# RPi-UKHASnet-node.net
KiCad netlist of a schematic drawn in EAGLE
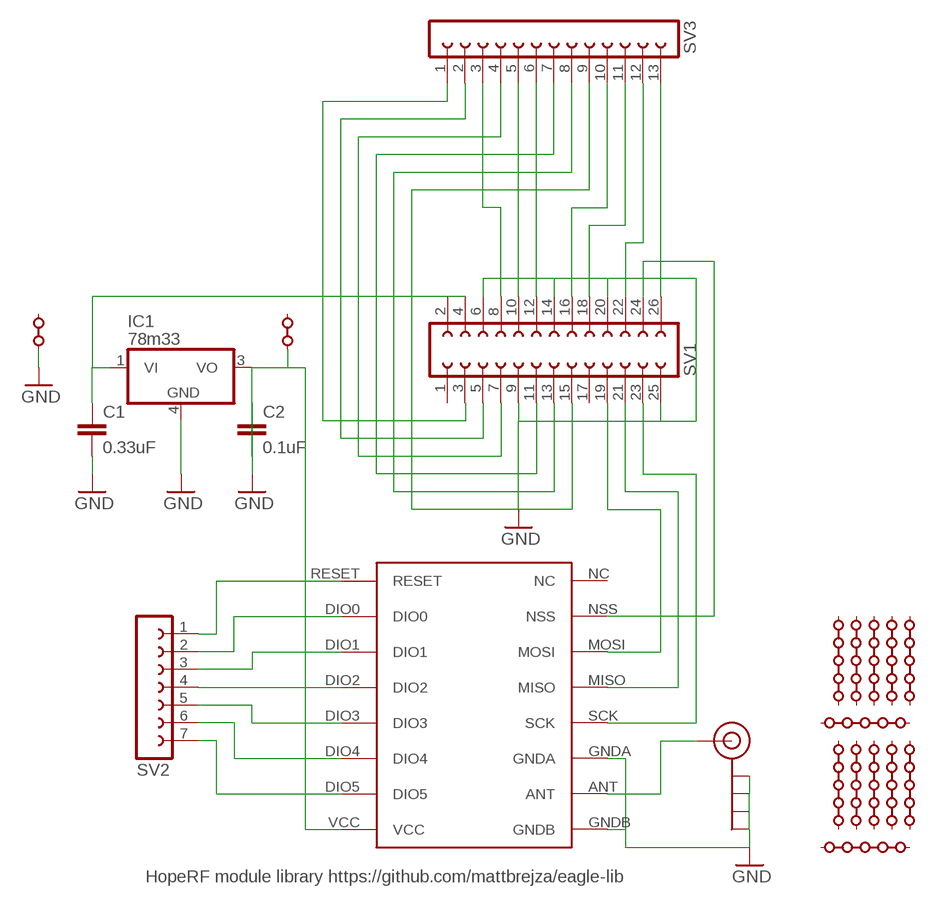
[diagram p0: schematic, sheet 1]

(export (version "E")
  (design (tool "Eeschema 10.0.6"))
  (components
    (comp (ref "C1")
      (value "0.33uF")
      (footprint "eagle-import:C1206")
      (libsource (lib "eagle-import") (part "C-EUC1206"))
    )
    (comp (ref "C2")
      (value "0.1uF")
      (footprint "eagle-import:C1206")
      (libsource (lib "eagle-import") (part "C-EUC1206"))
    )
    (comp (ref "IC1")
      (value "78m33")
      (footprint "eagle-import:SOT223")
      (libsource (lib "eagle-import") (part "LM340?-MP05"))
    )
    (comp (ref "J$1")
      (value "SMA_EDGE")
      (footprint "eagle-import:SMA-EDGE")
      (libsource (lib "eagle-import") (part "SMA_EDGE"))
    )
    (comp (ref "P1")
      (value "PADSTRIP5-VA")
      (footprint "eagle-import:PADSTRIP-5V")
      (libsource (lib "eagle-import") (part "PADSTRIP5-VA"))
    )
    (comp (ref "P2")
      (value "PADSTRIP5-VA")
      (footprint "eagle-import:PADSTRIP-5V")
      (libsource (lib "eagle-import") (part "PADSTRIP5-VA"))
    )
    (comp (ref "P3")
      (value "PADSTRIP5-VA")
      (footprint "eagle-import:PADSTRIP-5V")
      (libsource (lib "eagle-import") (part "PADSTRIP5-VA"))
    )
    (comp (ref "P4")
      (value "PADSTRIP5-VA")
      (footprint "eagle-import:PADSTRIP-5V")
      (libsource (lib "eagle-import") (part "PADSTRIP5-VA"))
    )
    (comp (ref "P5")
      (value "PADSTRIP5-VA")
      (footprint "eagle-import:PADSTRIP-5V")
      (libsource (lib "eagle-import") (part "PADSTRIP5-VA"))
    )
    (comp (ref "P9")
      (value "PADSTRIP5-VA")
      (footprint "eagle-import:PADSTRIP-5V")
      (libsource (lib "eagle-import") (part "PADSTRIP5-VA"))
    )
    (comp (ref "P10")
      (value "PADSTRIP5-VA")
      (footprint "eagle-import:PADSTRIP-5V")
      (libsource (lib "eagle-import") (part "PADSTRIP5-VA"))
    )
    (comp (ref "P11")
      (value "PADSTRIP5-VA")
      (footprint "eagle-import:PADSTRIP-5V")
      (libsource (lib "eagle-import") (part "PADSTRIP5-VA"))
    )
    (comp (ref "P12")
      (value "PADSTRIP5-VA")
      (footprint "eagle-import:PADSTRIP-5V")
      (libsource (lib "eagle-import") (part "PADSTRIP5-VA"))
    )
    (comp (ref "P13")
      (value "PADSTRIP5-VA")
      (footprint "eagle-import:PADSTRIP-5V")
      (libsource (lib "eagle-import") (part "PADSTRIP5-VA"))
    )
    (comp (ref "P17")
      (value "PADSTRIP5-VA")
      (footprint "eagle-import:PADSTRIP-5V")
      (libsource (lib "eagle-import") (part "PADSTRIP5-VA"))
    )
    (comp (ref "P18")
      (value "PADSTRIP5-VA")
      (footprint "eagle-import:PADSTRIP-5V")
      (libsource (lib "eagle-import") (part "PADSTRIP5-VA"))
    )
    (comp (ref "PR8")
      (value "PADSTRIP2-H")
      (footprint "eagle-import:PADSTRIP-2H")
      (libsource (lib "eagle-import") (part "PADSTRIP2-H"))
    )
    (comp (ref "PR20")
      (value "PADSTRIP2-H")
      (footprint "eagle-import:PADSTRIP-2H")
      (libsource (lib "eagle-import") (part "PADSTRIP2-H"))
    )
    (comp (ref "SV1")
      (value "FE13-2")
      (footprint "eagle-import:FE13-2")
      (libsource (lib "eagle-import") (part "FE13-2"))
    )
    (comp (ref "SV2")
      (value "FE07-1")
      (footprint "eagle-import:FE07")
      (libsource (lib "eagle-import") (part "FE07-1"))
    )
    (comp (ref "SV3")
      (value "FE13-1")
      (footprint "eagle-import:FE13")
      (libsource (lib "eagle-import") (part "FE13-1"))
    )
    (comp (ref "U1")
      (value "RFM69HW")
      (footprint "eagle-import:RFM")
      (libsource (lib "eagle-import") (part "RFM69HW"))
    )
  )
  (nets
    (net (code "1") (name "GND") (class "Default")
      (node (ref "C1") (pin "2") (pinfunction "2_2") (pintype "passive"))
      (node (ref "C2") (pin "1") (pinfunction "1_1") (pintype "passive"))
      (node (ref "IC1") (pin "4") (pinfunction "GND_4") (pintype "passive"))
      (node (ref "J$1") (pin "GND@0") (pinfunction "GND_GND@0") (pintype "bidirectional"))
      (node (ref "J$1") (pin "GND@1") (pinfunction "GND_GND@1") (pintype "bidirectional"))
      (node (ref "J$1") (pin "GND@2") (pinfunction "GND_GND@2") (pintype "bidirectional"))
      (node (ref "J$1") (pin "GND@3") (pinfunction "GND_GND@3") (pintype "bidirectional"))
      (node (ref "PR20") (pin "1") (pinfunction "LFT_1") (pintype "bidirectional"))
      (node (ref "SV1") (pin "14") (pinfunction "14_14") (pintype "passive"))
      (node (ref "SV1") (pin "20") (pinfunction "20_20") (pintype "passive"))
      (node (ref "SV1") (pin "25") (pinfunction "25_25") (pintype "passive"))
      (node (ref "SV1") (pin "6") (pinfunction "6_6") (pintype "passive"))
      (node (ref "SV1") (pin "9") (pinfunction "9_9") (pintype "passive"))
      (node (ref "U1") (pin "GNDA") (pinfunction "GNDA_GNDA") (pintype "bidirectional"))
      (node (ref "U1") (pin "GNDB") (pinfunction "GNDB_GNDB") (pintype "bidirectional"))
    )
    (net (code "2") (name "Net-(IC1-VI)") (class "Default")
      (node (ref "C1") (pin "1") (pinfunction "1_1") (pintype "passive"))
      (node (ref "IC1") (pin "1") (pinfunction "VI_1") (pintype "input"))
      (node (ref "SV1") (pin "2") (pinfunction "2_2") (pintype "passive"))
      (node (ref "SV1") (pin "4") (pinfunction "4_4") (pintype "passive"))
    )
    (net (code "3") (name "Net-(IC1-VO)") (class "Default")
      (node (ref "C2") (pin "2") (pinfunction "2_2") (pintype "passive"))
      (node (ref "IC1") (pin "3") (pinfunction "VO_3") (pintype "passive"))
      (node (ref "PR8") (pin "1") (pinfunction "LFT_1") (pintype "bidirectional"))
      (node (ref "U1") (pin "VCC") (pinfunction "VCC_VCC") (pintype "bidirectional"))
    )
    (net (code "4") (name "Net-(J$1-SIGNAL)") (class "Default")
      (node (ref "J$1") (pin "SIG") (pinfunction "SIGNAL_SIG") (pintype "bidirectional"))
      (node (ref "U1") (pin "ANT") (pinfunction "ANT_ANT") (pintype "bidirectional"))
    )
    (net (code "5") (name "Net-(SV1-Pad3)") (class "Default")
      (node (ref "SV1") (pin "3") (pinfunction "3_3") (pintype "passive"))
      (node (ref "SV3") (pin "1") (pinfunction "1_1") (pintype "passive"))
    )
    (net (code "6") (name "Net-(SV1-Pad5)") (class "Default")
      (node (ref "SV1") (pin "5") (pinfunction "5_5") (pintype "passive"))
      (node (ref "SV3") (pin "2") (pinfunction "2_2") (pintype "passive"))
    )
    (net (code "7") (name "Net-(SV1-Pad7)") (class "Default")
      (node (ref "SV1") (pin "7") (pinfunction "7_7") (pintype "passive"))
      (node (ref "SV3") (pin "4") (pinfunction "4_4") (pintype "passive"))
    )
    (net (code "8") (name "Net-(SV1-Pad8)") (class "Default")
      (node (ref "SV1") (pin "8") (pinfunction "8_8") (pintype "passive"))
      (node (ref "SV3") (pin "3") (pinfunction "3_3") (pintype "passive"))
    )
    (net (code "9") (name "Net-(SV1-Pad10)") (class "Default")
      (node (ref "SV1") (pin "10") (pinfunction "10_10") (pintype "passive"))
      (node (ref "SV3") (pin "5") (pinfunction "5_5") (pintype "passive"))
    )
    (net (code "10") (name "Net-(SV1-Pad11)") (class "Default")
      (node (ref "SV1") (pin "11") (pinfunction "11_11") (pintype "passive"))
      (node (ref "SV3") (pin "7") (pinfunction "7_7") (pintype "passive"))
    )
    (net (code "11") (name "Net-(SV1-Pad12)") (class "Default")
      (node (ref "SV1") (pin "12") (pinfunction "12_12") (pintype "passive"))
      (node (ref "SV3") (pin "6") (pinfunction "6_6") (pintype "passive"))
    )
    (net (code "12") (name "Net-(SV1-Pad13)") (class "Default")
      (node (ref "SV1") (pin "13") (pinfunction "13_13") (pintype "passive"))
      (node (ref "SV3") (pin "8") (pinfunction "8_8") (pintype "passive"))
    )
    (net (code "13") (name "Net-(SV1-Pad15)") (class "Default")
      (node (ref "SV1") (pin "15") (pinfunction "15_15") (pintype "passive"))
      (node (ref "SV3") (pin "9") (pinfunction "9_9") (pintype "passive"))
    )
    (net (code "14") (name "Net-(SV1-Pad16)") (class "Default")
      (node (ref "SV1") (pin "16") (pinfunction "16_16") (pintype "passive"))
      (node (ref "SV3") (pin "10") (pinfunction "10_10") (pintype "passive"))
    )
    (net (code "15") (name "Net-(SV1-Pad18)") (class "Default")
      (node (ref "SV1") (pin "18") (pinfunction "18_18") (pintype "passive"))
      (node (ref "SV3") (pin "11") (pinfunction "11_11") (pintype "passive"))
    )
    (net (code "16") (name "Net-(SV1-Pad19)") (class "Default")
      (node (ref "SV1") (pin "19") (pinfunction "19_19") (pintype "passive"))
      (node (ref "U1") (pin "MOSI") (pinfunction "MOSI_MOSI") (pintype "bidirectional"))
    )
    (net (code "17") (name "Net-(SV1-Pad21)") (class "Default")
      (node (ref "SV1") (pin "21") (pinfunction "21_21") (pintype "passive"))
      (node (ref "U1") (pin "MISO") (pinfunction "MISO_MISO") (pintype "bidirectional"))
    )
    (net (code "18") (name "Net-(SV1-Pad22)") (class "Default")
      (node (ref "SV1") (pin "22") (pinfunction "22_22") (pintype "passive"))
      (node (ref "SV3") (pin "12") (pinfunction "12_12") (pintype "passive"))
    )
    (net (code "19") (name "Net-(SV1-Pad23)") (class "Default")
      (node (ref "SV1") (pin "23") (pinfunction "23_23") (pintype "passive"))
      (node (ref "U1") (pin "SCK") (pinfunction "SCK_SCK") (pintype "bidirectional"))
    )
    (net (code "20") (name "Net-(SV1-Pad24)") (class "Default")
      (node (ref "SV1") (pin "24") (pinfunction "24_24") (pintype "passive"))
      (node (ref "U1") (pin "NSS") (pinfunction "NSS_NSS") (pintype "bidirectional"))
    )
    (net (code "21") (name "Net-(SV1-Pad26)") (class "Default")
      (node (ref "SV1") (pin "26") (pinfunction "26_26") (pintype "passive"))
      (node (ref "SV3") (pin "13") (pinfunction "13_13") (pintype "passive"))
    )
    (net (code "22") (name "Net-(SV2-Pad1)") (class "Default")
      (node (ref "SV2") (pin "1") (pinfunction "1_1") (pintype "passive"))
      (node (ref "U1") (pin "RESET") (pinfunction "RESET_RESET") (pintype "bidirectional"))
    )
    (net (code "23") (name "Net-(SV2-Pad2)") (class "Default")
      (node (ref "SV2") (pin "2") (pinfunction "2_2") (pintype "passive"))
      (node (ref "U1") (pin "DIO0") (pinfunction "DIO0_DIO0") (pintype "bidirectional"))
    )
    (net (code "24") (name "Net-(SV2-Pad3)") (class "Default")
      (node (ref "SV2") (pin "3") (pinfunction "3_3") (pintype "passive"))
      (node (ref "U1") (pin "DIO1") (pinfunction "DIO1_DIO1") (pintype "bidirectional"))
    )
    (net (code "25") (name "Net-(SV2-Pad4)") (class "Default")
      (node (ref "SV2") (pin "4") (pinfunction "4_4") (pintype "passive"))
      (node (ref "U1") (pin "DIO2") (pinfunction "DIO2_DIO2") (pintype "bidirectional"))
    )
    (net (code "26") (name "Net-(SV2-Pad5)") (class "Default")
      (node (ref "SV2") (pin "5") (pinfunction "5_5") (pintype "passive"))
      (node (ref "U1") (pin "DIO3") (pinfunction "DIO3_DIO3") (pintype "bidirectional"))
    )
    (net (code "27") (name "Net-(SV2-Pad6)") (class "Default")
      (node (ref "SV2") (pin "6") (pinfunction "6_6") (pintype "passive"))
      (node (ref "U1") (pin "DIO4") (pinfunction "DIO4_DIO4") (pintype "bidirectional"))
    )
    (net (code "28") (name "Net-(SV2-Pad7)") (class "Default")
      (node (ref "SV2") (pin "7") (pinfunction "7_7") (pintype "passive"))
      (node (ref "U1") (pin "DIO5") (pinfunction "DIO5_DIO5") (pintype "bidirectional"))
    )
    (net (code "29") (name "unconnected-(P1-Pad1)") (class "Default")
      (node (ref "P1") (pin "1") (pinfunction "1_1") (pintype "bidirectional"))
    )
    (net (code "30") (name "unconnected-(P1-Pad5)") (class "Default")
      (node (ref "P1") (pin "5") (pinfunction "5_5") (pintype "bidirectional"))
    )
    (net (code "31") (name "unconnected-(P2-Pad1)") (class "Default")
      (node (ref "P2") (pin "1") (pinfunction "1_1") (pintype "bidirectional"))
    )
    (net (code "32") (name "unconnected-(P2-Pad5)") (class "Default")
      (node (ref "P2") (pin "5") (pinfunction "5_5") (pintype "bidirectional"))
    )
    (net (code "33") (name "unconnected-(P3-Pad1)") (class "Default")
      (node (ref "P3") (pin "1") (pinfunction "1_1") (pintype "bidirectional"))
    )
    (net (code "34") (name "unconnected-(P3-Pad5)") (class "Default")
      (node (ref "P3") (pin "5") (pinfunction "5_5") (pintype "bidirectional"))
    )
    (net (code "35") (name "unconnected-(P4-Pad1)") (class "Default")
      (node (ref "P4") (pin "1") (pinfunction "1_1") (pintype "bidirectional"))
    )
    (net (code "36") (name "unconnected-(P4-Pad5)") (class "Default")
      (node (ref "P4") (pin "5") (pinfunction "5_5") (pintype "bidirectional"))
    )
    (net (code "37") (name "unconnected-(P5-Pad1)") (class "Default")
      (node (ref "P5") (pin "1") (pinfunction "1_1") (pintype "bidirectional"))
    )
    (net (code "38") (name "unconnected-(P5-Pad5)") (class "Default")
      (node (ref "P5") (pin "5") (pinfunction "5_5") (pintype "bidirectional"))
    )
    (net (code "39") (name "unconnected-(P9-Pad1)") (class "Default")
      (node (ref "P9") (pin "1") (pinfunction "1_1") (pintype "bidirectional"))
    )
    (net (code "40") (name "unconnected-(P9-Pad5)") (class "Default")
      (node (ref "P9") (pin "5") (pinfunction "5_5") (pintype "bidirectional"))
    )
    (net (code "41") (name "unconnected-(P10-Pad1)") (class "Default")
      (node (ref "P10") (pin "1") (pinfunction "1_1") (pintype "bidirectional"))
    )
    (net (code "42") (name "unconnected-(P10-Pad5)") (class "Default")
      (node (ref "P10") (pin "5") (pinfunction "5_5") (pintype "bidirectional"))
    )
    (net (code "43") (name "unconnected-(P11-Pad1)") (class "Default")
      (node (ref "P11") (pin "1") (pinfunction "1_1") (pintype "bidirectional"))
    )
    (net (code "44") (name "unconnected-(P11-Pad5)") (class "Default")
      (node (ref "P11") (pin "5") (pinfunction "5_5") (pintype "bidirectional"))
    )
    (net (code "45") (name "unconnected-(P12-Pad1)") (class "Default")
      (node (ref "P12") (pin "1") (pinfunction "1_1") (pintype "bidirectional"))
    )
    (net (code "46") (name "unconnected-(P12-Pad5)") (class "Default")
      (node (ref "P12") (pin "5") (pinfunction "5_5") (pintype "bidirectional"))
    )
    (net (code "47") (name "unconnected-(P13-Pad1)") (class "Default")
      (node (ref "P13") (pin "1") (pinfunction "1_1") (pintype "bidirectional"))
    )
    (net (code "48") (name "unconnected-(P13-Pad5)") (class "Default")
      (node (ref "P13") (pin "5") (pinfunction "5_5") (pintype "bidirectional"))
    )
    (net (code "49") (name "unconnected-(P17-Pad1)") (class "Default")
      (node (ref "P17") (pin "1") (pinfunction "1_1") (pintype "bidirectional"))
    )
    (net (code "50") (name "unconnected-(P17-Pad5)") (class "Default")
      (node (ref "P17") (pin "5") (pinfunction "5_5") (pintype "bidirectional"))
    )
    (net (code "51") (name "unconnected-(P18-Pad1)") (class "Default")
      (node (ref "P18") (pin "1") (pinfunction "1_1") (pintype "bidirectional"))
    )
    (net (code "52") (name "unconnected-(P18-Pad5)") (class "Default")
      (node (ref "P18") (pin "5") (pinfunction "5_5") (pintype "bidirectional"))
    )
    (net (code "53") (name "unconnected-(PR8-RIT-Pad2)") (class "Default")
      (node (ref "PR8") (pin "2") (pinfunction "RIT_2") (pintype "bidirectional"))
    )
    (net (code "54") (name "unconnected-(PR20-RIT-Pad2)") (class "Default")
      (node (ref "PR20") (pin "2") (pinfunction "RIT_2") (pintype "bidirectional"))
    )
    (net (code "55") (name "unconnected-(SV1-Pad1)") (class "Default")
      (node (ref "SV1") (pin "1") (pinfunction "1_1") (pintype "passive"))
    )
    (net (code "56") (name "unconnected-(SV1-Pad17)") (class "Default")
      (node (ref "SV1") (pin "17") (pinfunction "17_17") (pintype "passive"))
    )
    (net (code "57") (name "unconnected-(U1-PadNC)") (class "Default")
      (node (ref "U1") (pin "NC") (pinfunction "NC_NC") (pintype "bidirectional"))
    )
  )
)
